# main.net
KiCad netlist of a schematic drawn in EAGLE
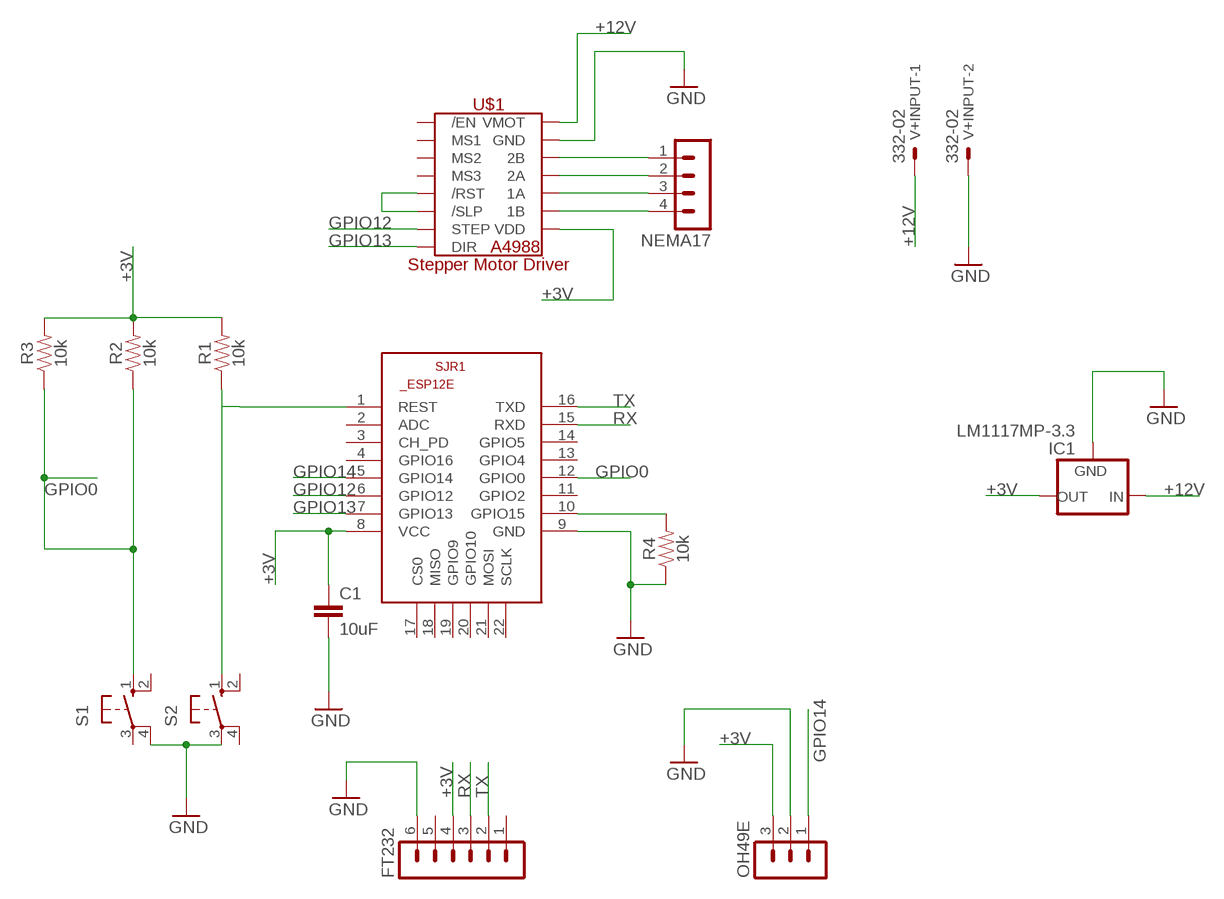
[diagram p0: schematic, sheet 1]

(export (version "E")
  (design (tool "Eeschema 10.0.6"))
  (components
    (comp (ref "C1")
      (value "10uF")
      (footprint "eagle-import:C1206")
      (libsource (lib "eagle-import") (part "CC1206"))
    )
    (comp (ref "FT232")
      (value "MA06-1")
      (footprint "eagle-import:MA06-1")
      (libsource (lib "eagle-import") (part "MA06-1"))
    )
    (comp (ref "IC1")
      (value "LM1117MP-3.3")
      (footprint "eagle-import:SOT223")
      (fields (field (name "MF") "Texas Instruments"))
      (libsource (lib "eagle-import") (part "LM1117?-MP3.3"))
    )
    (comp (ref "NEMA17")
      (value "MA04-1")
      (footprint "eagle-import:MA04-1")
      (libsource (lib "eagle-import") (part "MA04-1"))
    )
    (comp (ref "OH49E")
      (value "MA03-1")
      (footprint "eagle-import:MA03-1")
      (libsource (lib "eagle-import") (part "MA03-1"))
    )
    (comp (ref "R1")
      (value "10k")
      (footprint "eagle-import:0603")
      (libsource (lib "eagle-import") (part "10KOHM-0603-1/10W-1%"))
    )
    (comp (ref "R2")
      (value "10k")
      (footprint "eagle-import:0603")
      (libsource (lib "eagle-import") (part "10KOHM-0603-1/10W-1%"))
    )
    (comp (ref "R3")
      (value "10k")
      (footprint "eagle-import:0603")
      (libsource (lib "eagle-import") (part "10KOHM-0603-1/10W-1%"))
    )
    (comp (ref "R4")
      (value "10k")
      (footprint "eagle-import:0603")
      (libsource (lib "eagle-import") (part "10KOHM-0603-1/10W-1%"))
    )
    (comp (ref "S1")
      (value "10-XX")
      (footprint "eagle-import:B3F-10XX")
      (fields (field (name "MPN") "B3F-1000"))
      (libsource (lib "eagle-import") (part "10-XX"))
    )
    (comp (ref "S2")
      (value "10-XX")
      (footprint "eagle-import:B3F-10XX")
      (fields (field (name "MPN") "B3F-1000"))
      (libsource (lib "eagle-import") (part "10-XX"))
    )
    (comp (ref "SJR1")
      (value "ESP8266-12EESP12E")
      (footprint "eagle-import:ESP8266-ESP12E")
      (libsource (lib "eagle-import") (part "ESP8266-12EESP12E"))
    )
    (comp (ref "U$1")
      (value "A4988_STEP")
      (footprint "eagle-import:A4988_STEP")
      (libsource (lib "eagle-import") (part "A4988_STEP"))
    )
    (comp (ref "V+INPUT")
      (value "332-02")
      (footprint "eagle-import:332-02")
      (libsource (lib "eagle-import") (part "332-02"))
    )
  )
  (nets
    (net (code "1") (name "/+3V") (class "Default")
      (node (ref "C1") (pin "1") (pinfunction "1_1") (pintype "passive"))
      (node (ref "FT232") (pin "4") (pinfunction "4_4") (pintype "passive"))
      (node (ref "IC1") (pin "2") (pinfunction "OUT_2") (pintype "passive"))
      (node (ref "IC1") (pin "4") (pinfunction "OUT_4") (pintype "passive"))
      (node (ref "OH49E") (pin "3") (pinfunction "3_3") (pintype "passive"))
      (node (ref "R1") (pin "2") (pinfunction "2_2") (pintype "passive"))
      (node (ref "R2") (pin "2") (pinfunction "2_2") (pintype "passive"))
      (node (ref "R3") (pin "2") (pinfunction "2_2") (pintype "passive"))
      (node (ref "SJR1") (pin "8") (pinfunction "VCC_8") (pintype "bidirectional"))
      (node (ref "U$1") (pin "VDD") (pinfunction "VDD_VDD") (pintype "bidirectional"))
    )
    (net (code "2") (name "/+12V") (class "Default")
      (node (ref "IC1") (pin "3") (pinfunction "IN_3") (pintype "input"))
      (node (ref "U$1") (pin "VMOT") (pinfunction "VMOT_VMOT") (pintype "bidirectional"))
      (node (ref "V+INPUT") (pin "1") (pinfunction "S_1") (pintype "passive"))
    )
    (net (code "3") (name "/GPIO0") (class "Default")
      (node (ref "R2") (pin "1") (pinfunction "1_1") (pintype "passive"))
      (node (ref "R3") (pin "1") (pinfunction "1_1") (pintype "passive"))
      (node (ref "S1") (pin "1") (pinfunction "S_1") (pintype "passive"))
      (node (ref "SJR1") (pin "12") (pinfunction "GPIO0_12") (pintype "bidirectional"))
    )
    (net (code "4") (name "/GPIO12") (class "Default")
      (node (ref "SJR1") (pin "6") (pinfunction "GPIO12_6") (pintype "bidirectional"))
      (node (ref "U$1") (pin "STEP") (pinfunction "STEP_STEP") (pintype "bidirectional"))
    )
    (net (code "5") (name "/GPIO13") (class "Default")
      (node (ref "SJR1") (pin "7") (pinfunction "GPIO13_7") (pintype "bidirectional"))
      (node (ref "U$1") (pin "DIR") (pinfunction "DIR_DIR") (pintype "bidirectional"))
    )
    (net (code "6") (name "/GPIO14") (class "Default")
      (node (ref "OH49E") (pin "1") (pinfunction "1_1") (pintype "passive"))
      (node (ref "SJR1") (pin "5") (pinfunction "GPIO14_5") (pintype "bidirectional"))
    )
    (net (code "7") (name "/RX") (class "Default")
      (node (ref "FT232") (pin "3") (pinfunction "3_3") (pintype "passive"))
      (node (ref "SJR1") (pin "15") (pinfunction "RXD_15") (pintype "bidirectional"))
    )
    (net (code "8") (name "/TX") (class "Default")
      (node (ref "FT232") (pin "2") (pinfunction "2_2") (pintype "passive"))
      (node (ref "SJR1") (pin "16") (pinfunction "TXD_16") (pintype "bidirectional"))
    )
    (net (code "9") (name "GND") (class "Default")
      (node (ref "C1") (pin "2") (pinfunction "2_2") (pintype "passive"))
      (node (ref "FT232") (pin "6") (pinfunction "6_6") (pintype "passive"))
      (node (ref "IC1") (pin "1") (pinfunction "GND_1") (pintype "input"))
      (node (ref "OH49E") (pin "2") (pinfunction "2_2") (pintype "passive"))
      (node (ref "R4") (pin "1") (pinfunction "1_1") (pintype "passive"))
      (node (ref "S1") (pin "4") (pinfunction "P1_4") (pintype "passive"))
      (node (ref "S2") (pin "3") (pinfunction "P_3") (pintype "passive"))
      (node (ref "SJR1") (pin "9") (pinfunction "GND_9") (pintype "bidirectional"))
      (node (ref "U$1") (pin "GND") (pinfunction "GND_GND") (pintype "bidirectional"))
      (node (ref "U$1") (pin "GND2") (pinfunction "GND_GND2") (pintype "bidirectional"))
      (node (ref "V+INPUT") (pin "2") (pinfunction "S_2") (pintype "passive"))
    )
    (net (code "10") (name "Net-(NEMA17-Pad1)") (class "Default")
      (node (ref "NEMA17") (pin "1") (pinfunction "1_1") (pintype "passive"))
      (node (ref "U$1") (pin "2B") (pinfunction "2B_2B") (pintype "bidirectional"))
    )
    (net (code "11") (name "Net-(NEMA17-Pad2)") (class "Default")
      (node (ref "NEMA17") (pin "2") (pinfunction "2_2") (pintype "passive"))
      (node (ref "U$1") (pin "2A") (pinfunction "2A_2A") (pintype "bidirectional"))
    )
    (net (code "12") (name "Net-(NEMA17-Pad3)") (class "Default")
      (node (ref "NEMA17") (pin "3") (pinfunction "3_3") (pintype "passive"))
      (node (ref "U$1") (pin "1A") (pinfunction "1A_1A") (pintype "bidirectional"))
    )
    (net (code "13") (name "Net-(NEMA17-Pad4)") (class "Default")
      (node (ref "NEMA17") (pin "4") (pinfunction "4_4") (pintype "passive"))
      (node (ref "U$1") (pin "1B") (pinfunction "1B_1B") (pintype "bidirectional"))
    )
    (net (code "14") (name "Net-(S2-S)") (class "Default")
      (node (ref "R1") (pin "1") (pinfunction "1_1") (pintype "passive"))
      (node (ref "S2") (pin "1") (pinfunction "S_1") (pintype "passive"))
      (node (ref "SJR1") (pin "1") (pinfunction "REST_1") (pintype "bidirectional"))
    )
    (net (code "15") (name "Net-(SJR1-GPIO15)") (class "Default")
      (node (ref "R4") (pin "2") (pinfunction "2_2") (pintype "passive"))
      (node (ref "SJR1") (pin "10") (pinfunction "GPIO15_10") (pintype "bidirectional"))
    )
    (net (code "16") (name "Net-(U$1-Pad{slash}RST)") (class "Default")
      (node (ref "U$1") (pin "/RST") (pinfunction "/RST_/RST") (pintype "bidirectional"))
      (node (ref "U$1") (pin "/SLP") (pinfunction "/SLP_/SLP") (pintype "bidirectional"))
    )
    (net (code "17") (name "unconnected-(FT232-Pad1)") (class "Default")
      (node (ref "FT232") (pin "1") (pinfunction "1_1") (pintype "passive"))
    )
    (net (code "18") (name "unconnected-(FT232-Pad5)") (class "Default")
      (node (ref "FT232") (pin "5") (pinfunction "5_5") (pintype "passive"))
    )
    (net (code "19") (name "unconnected-(S1-P-Pad3)") (class "Default")
      (node (ref "S1") (pin "3") (pinfunction "P_3") (pintype "passive"))
    )
    (net (code "20") (name "unconnected-(S1-S1-Pad2)") (class "Default")
      (node (ref "S1") (pin "2") (pinfunction "S1_2") (pintype "passive"))
    )
    (net (code "21") (name "unconnected-(S2-P1-Pad4)") (class "Default")
      (node (ref "S2") (pin "4") (pinfunction "P1_4") (pintype "passive"))
    )
    (net (code "22") (name "unconnected-(S2-S1-Pad2)") (class "Default")
      (node (ref "S2") (pin "2") (pinfunction "S1_2") (pintype "passive"))
    )
    (net (code "23") (name "unconnected-(SJR1-ADC-Pad2)") (class "Default")
      (node (ref "SJR1") (pin "2") (pinfunction "ADC_2") (pintype "bidirectional"))
    )
    (net (code "24") (name "unconnected-(SJR1-CH_PD-Pad3)") (class "Default")
      (node (ref "SJR1") (pin "3") (pinfunction "CH_PD_3") (pintype "bidirectional"))
    )
    (net (code "25") (name "unconnected-(SJR1-CS0-Pad17)") (class "Default")
      (node (ref "SJR1") (pin "17") (pinfunction "CS0_17") (pintype "bidirectional"))
    )
    (net (code "26") (name "unconnected-(SJR1-GPIO2-Pad11)") (class "Default")
      (node (ref "SJR1") (pin "11") (pinfunction "GPIO2_11") (pintype "bidirectional"))
    )
    (net (code "27") (name "unconnected-(SJR1-GPIO4-Pad13)") (class "Default")
      (node (ref "SJR1") (pin "13") (pinfunction "GPIO4_13") (pintype "bidirectional"))
    )
    (net (code "28") (name "unconnected-(SJR1-GPIO5-Pad14)") (class "Default")
      (node (ref "SJR1") (pin "14") (pinfunction "GPIO5_14") (pintype "bidirectional"))
    )
    (net (code "29") (name "unconnected-(SJR1-GPIO9-Pad19)") (class "Default")
      (node (ref "SJR1") (pin "19") (pinfunction "GPIO9_19") (pintype "bidirectional"))
    )
    (net (code "30") (name "unconnected-(SJR1-GPIO10-Pad20)") (class "Default")
      (node (ref "SJR1") (pin "20") (pinfunction "GPIO10_20") (pintype "bidirectional"))
    )
    (net (code "31") (name "unconnected-(SJR1-GPIO16-Pad4)") (class "Default")
      (node (ref "SJR1") (pin "4") (pinfunction "GPIO16_4") (pintype "bidirectional"))
    )
    (net (code "32") (name "unconnected-(SJR1-MISO-Pad18)") (class "Default")
      (node (ref "SJR1") (pin "18") (pinfunction "MISO_18") (pintype "bidirectional"))
    )
    (net (code "33") (name "unconnected-(SJR1-MOSI-Pad21)") (class "Default")
      (node (ref "SJR1") (pin "21") (pinfunction "MOSI_21") (pintype "bidirectional"))
    )
    (net (code "34") (name "unconnected-(SJR1-SCLK-Pad22)") (class "Default")
      (node (ref "SJR1") (pin "22") (pinfunction "SCLK_22") (pintype "bidirectional"))
    )
    (net (code "35") (name "unconnected-(U$1-PadMS1)") (class "Default")
      (node (ref "U$1") (pin "MS1") (pinfunction "MS1_MS1") (pintype "bidirectional"))
    )
    (net (code "36") (name "unconnected-(U$1-PadMS2)") (class "Default")
      (node (ref "U$1") (pin "MS2") (pinfunction "MS2_MS2") (pintype "bidirectional"))
    )
    (net (code "37") (name "unconnected-(U$1-PadMS3)") (class "Default")
      (node (ref "U$1") (pin "MS3") (pinfunction "MS3_MS3") (pintype "bidirectional"))
    )
    (net (code "38") (name "unconnected-(U$1-Pad{slash}EN)") (class "Default")
      (node (ref "U$1") (pin "/EN") (pinfunction "/EN_/EN") (pintype "bidirectional"))
    )
  )
)
